# iso_GPIO_4in_4out.net
KiCad netlist of a schematic drawn in Altium Designer
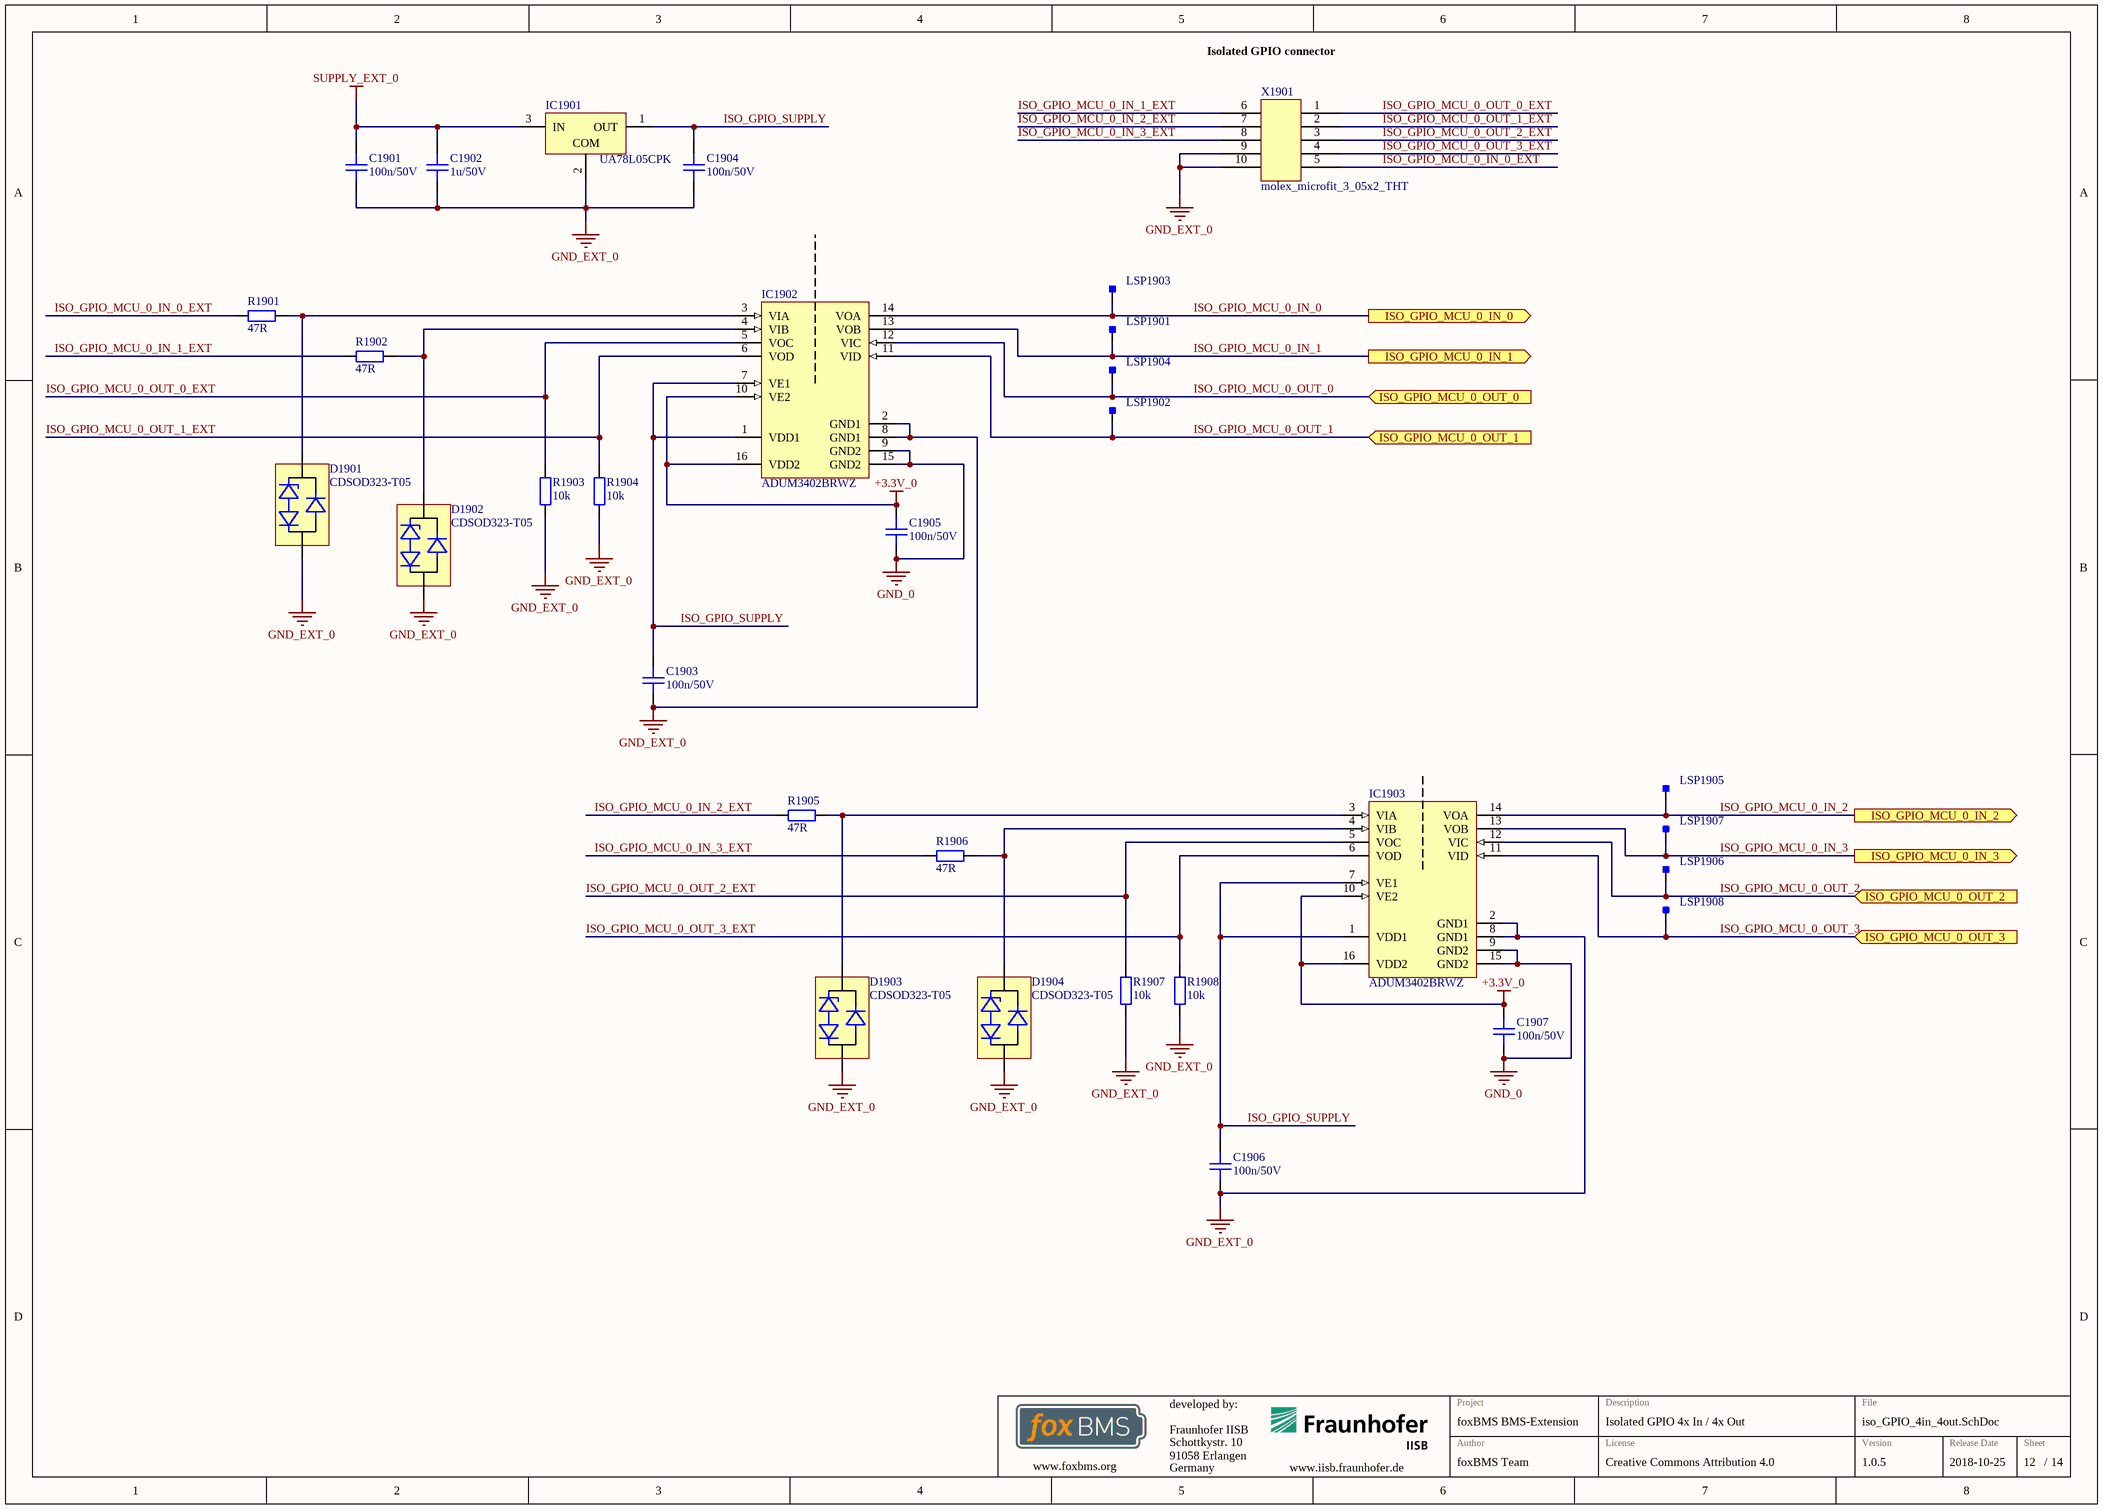
[diagram p0: iso_GPIO_4in_4out.SchDoc]

(export (version "E")
  (design (tool "Eeschema 10.0.6"))
  (components
    (comp (ref "C1901")
      (value "100n/50V")
      (footprint "CAPC1608X08N")
      (description "MLCC")
      (fields (field (name "PART NUMBER") "gen_C_ceramic_100n_50V_X7R_0603"))
      (libsource (lib "OE750") (part "C"))
    )
    (comp (ref "C1902")
      (value "1u/50V")
      (footprint "CAPC1608X08N")
      (description "MLCC")
      (fields (field (name "PART NUMBER") "gen_C_ceramic_1u_50V_X7R_0603") (field (name "TOLERANCE") "± 10%"))
      (libsource (lib "OE750") (part "C"))
    )
    (comp (ref "C1903")
      (value "100n/50V")
      (footprint "CAPC1608X08N")
      (description "MLCC")
      (fields (field (name "PART NUMBER") "gen_C_ceramic_100n_50V_X7R_0603"))
      (libsource (lib "OE750") (part "C"))
    )
    (comp (ref "C1904")
      (value "100n/50V")
      (footprint "CAPC1608X08N")
      (description "MLCC")
      (fields (field (name "PART NUMBER") "gen_C_ceramic_100n_50V_X7R_0603"))
      (libsource (lib "OE750") (part "C"))
    )
    (comp (ref "C1905")
      (value "100n/50V")
      (footprint "CAPC1608X08N")
      (description "MLCC")
      (fields (field (name "PART NUMBER") "gen_C_ceramic_100n_50V_X7R_0603"))
      (libsource (lib "OE750") (part "C"))
    )
    (comp (ref "C1906")
      (value "100n/50V")
      (footprint "CAPC1608X08N")
      (description "MLCC")
      (fields (field (name "PART NUMBER") "gen_C_ceramic_100n_50V_X7R_0603"))
      (libsource (lib "OE750") (part "C"))
    )
    (comp (ref "C1907")
      (value "100n/50V")
      (footprint "CAPC1608X08N")
      (description "MLCC")
      (fields (field (name "PART NUMBER") "gen_C_ceramic_100n_50V_X7R_0603"))
      (libsource (lib "OE750") (part "C"))
    )
    (comp (ref "D1901")
      (value "CDSOD323-T05")
      (footprint "SODFL250X110-2N")
      (description "TVS Diode, CDSOD323 Series, Unidirectional, 5 V, 18.3 V, SOD-323, 2 Pins")
      (fields (field (name "MANUFACTURER") "Bourns"))
      (libsource (lib "OE750") (part "D_TVS_uni"))
    )
    (comp (ref "D1902")
      (value "CDSOD323-T05")
      (footprint "SODFL250X110-2N")
      (description "TVS Diode, CDSOD323 Series, Unidirectional, 5 V, 18.3 V, SOD-323, 2 Pins")
      (fields (field (name "MANUFACTURER") "Bourns"))
      (libsource (lib "OE750") (part "D_TVS_uni"))
    )
    (comp (ref "D1903")
      (value "CDSOD323-T05")
      (footprint "SODFL250X110-2N")
      (description "TVS Diode, CDSOD323 Series, Unidirectional, 5 V, 18.3 V, SOD-323, 2 Pins")
      (fields (field (name "MANUFACTURER") "Bourns"))
      (libsource (lib "OE750") (part "D_TVS_uni"))
    )
    (comp (ref "D1904")
      (value "CDSOD323-T05")
      (footprint "SODFL250X110-2N")
      (description "TVS Diode, CDSOD323 Series, Unidirectional, 5 V, 18.3 V, SOD-323, 2 Pins")
      (fields (field (name "MANUFACTURER") "Bourns"))
      (libsource (lib "OE750") (part "D_TVS_uni"))
    )
    (comp (ref "IC1901")
      (value "UA78L05CPK")
      (footprint "PK0003A_L")
      (fields (field (name "MANUFACTURER") "TexasInstruments"))
      (libsource (lib "Altium Content Vault") (part "TI-UA78L05-PK-3"))
    )
    (comp (ref "IC1902")
      (value "ADUM3402BRWZ")
      (footprint "ADI-RW-16_N")
      (fields (field (name "MANUFACTURER") "Analog Devices"))
      (libsource (lib "Altium Content Vault") (part "ADI-ADUMXXX2-XX-16"))
    )
    (comp (ref "IC1903")
      (value "ADUM3402BRWZ")
      (footprint "ADI-RW-16_N")
      (fields (field (name "MANUFACTURER") "Analog Devices"))
      (libsource (lib "Altium Content Vault") (part "ADI-ADUMXXX2-XX-16"))
    )
    (comp (ref "LSP1901")
      (value "Testpoint_Square")
      (footprint "Testpoint_S1")
      (description "Testpoint, square")
      (libsource (lib "OE750") (part "Testpoint_Square"))
    )
    (comp (ref "LSP1902")
      (value "Testpoint_Square")
      (footprint "Testpoint_S1")
      (description "Testpoint, square")
      (libsource (lib "OE750") (part "Testpoint_Square"))
    )
    (comp (ref "LSP1903")
      (value "Testpoint_Square")
      (footprint "Testpoint_S1")
      (description "Testpoint, square")
      (libsource (lib "OE750") (part "Testpoint_Square"))
    )
    (comp (ref "LSP1904")
      (value "Testpoint_Square")
      (footprint "Testpoint_S1")
      (description "Testpoint, square")
      (libsource (lib "OE750") (part "Testpoint_Square"))
    )
    (comp (ref "LSP1905")
      (value "Testpoint_Square")
      (footprint "Testpoint_S1")
      (description "Testpoint, square")
      (libsource (lib "OE750") (part "Testpoint_Square"))
    )
    (comp (ref "LSP1906")
      (value "Testpoint_Square")
      (footprint "Testpoint_S1")
      (description "Testpoint, square")
      (libsource (lib "OE750") (part "Testpoint_Square"))
    )
    (comp (ref "LSP1907")
      (value "Testpoint_Square")
      (footprint "Testpoint_S1")
      (description "Testpoint, square")
      (libsource (lib "OE750") (part "Testpoint_Square"))
    )
    (comp (ref "LSP1908")
      (value "Testpoint_Square")
      (footprint "Testpoint_S1")
      (description "Testpoint, square")
      (libsource (lib "OE750") (part "Testpoint_Square"))
    )
    (comp (ref "R1901")
      (value "47R")
      (footprint "RESC1608X05N")
      (description "SMD Resistor 47R 0603")
      (fields (field (name "PART NUMBER") "gen_R_47R_0603") (field (name "TOLERANCE") "1%"))
      (libsource (lib "OE750") (part "R"))
    )
    (comp (ref "R1902")
      (value "47R")
      (footprint "RESC1608X05N")
      (description "SMD Resistor 47R 0603")
      (fields (field (name "PART NUMBER") "gen_R_47R_0603") (field (name "TOLERANCE") "1%"))
      (libsource (lib "OE750") (part "R"))
    )
    (comp (ref "R1903")
      (value "10k")
      (footprint "RESC1608X05N")
      (description "SMD Resistor 10k 0603")
      (fields (field (name "PART NUMBER") "gen_R_10k_0603") (field (name "TOLERANCE") "1%"))
      (libsource (lib "OE750") (part "R"))
    )
    (comp (ref "R1904")
      (value "10k")
      (footprint "RESC1608X05N")
      (description "SMD Resistor 10k 0603")
      (fields (field (name "PART NUMBER") "gen_R_10k_0603") (field (name "TOLERANCE") "1%"))
      (libsource (lib "OE750") (part "R"))
    )
    (comp (ref "R1905")
      (value "47R")
      (footprint "RESC1608X05N")
      (description "SMD Resistor 47R 0603")
      (fields (field (name "PART NUMBER") "gen_R_47R_0603") (field (name "TOLERANCE") "1%"))
      (libsource (lib "OE750") (part "R"))
    )
    (comp (ref "R1906")
      (value "47R")
      (footprint "RESC1608X05N")
      (description "SMD Resistor 47R 0603")
      (fields (field (name "PART NUMBER") "gen_R_47R_0603") (field (name "TOLERANCE") "1%"))
      (libsource (lib "OE750") (part "R"))
    )
    (comp (ref "R1907")
      (value "10k")
      (footprint "RESC1608X05N")
      (description "SMD Resistor 10k 0603")
      (fields (field (name "PART NUMBER") "gen_R_10k_0603") (field (name "TOLERANCE") "1%"))
      (libsource (lib "OE750") (part "R"))
    )
    (comp (ref "R1908")
      (value "10k")
      (footprint "RESC1608X05N")
      (description "SMD Resistor 10k 0603")
      (fields (field (name "PART NUMBER") "gen_R_10k_0603") (field (name "TOLERANCE") "1%"))
      (libsource (lib "OE750") (part "R"))
    )
    (comp (ref "X1901")
      (value "molex_microfit_3_05x2_THT")
      (footprint "43045-1021")
      (fields (field (name "MANUFACTURER") "Molex"))
      (libsource (lib "OE750") (part "X5x2"))
    )
  )
  (nets
    (net (code "1") (name "+3.3V_0") (class "Default")
      (node (ref "C1905") (pin "1") (pinfunction "1_1") (pintype "passive"))
      (node (ref "C1907") (pin "1") (pinfunction "1_1") (pintype "passive"))
      (node (ref "IC1902") (pin "10") (pinfunction "VE2_10") (pintype "input"))
      (node (ref "IC1902") (pin "16") (pinfunction "VDD2_16") (pintype "power_in"))
      (node (ref "IC1903") (pin "10") (pinfunction "VE2_10") (pintype "input"))
      (node (ref "IC1903") (pin "16") (pinfunction "VDD2_16") (pintype "power_in"))
    )
    (net (code "2") (name "/ISO_GPIO_MCU_0_IN_0") (class "Default")
      (node (ref "IC1902") (pin "14") (pinfunction "VOA_14") (pintype "tri_state"))
      (node (ref "LSP1903") (pin "1") (pinfunction "1_1") (pintype "passive"))
    )
    (net (code "3") (name "/ISO_GPIO_MCU_0_IN_0_EXT") (class "Default")
      (node (ref "R1901") (pin "2") (pinfunction "2_2") (pintype "passive"))
      (node (ref "X1901") (pin "5") (pintype "passive"))
    )
    (net (code "4") (name "/ISO_GPIO_MCU_0_IN_1") (class "Default")
      (node (ref "IC1902") (pin "13") (pinfunction "VOB_13") (pintype "tri_state"))
      (node (ref "LSP1901") (pin "1") (pinfunction "1_1") (pintype "passive"))
    )
    (net (code "5") (name "/ISO_GPIO_MCU_0_IN_1_EXT") (class "Default")
      (node (ref "R1902") (pin "2") (pinfunction "2_2") (pintype "passive"))
      (node (ref "X1901") (pin "6") (pintype "passive"))
    )
    (net (code "6") (name "/ISO_GPIO_MCU_0_IN_2") (class "Default")
      (node (ref "IC1903") (pin "14") (pinfunction "VOA_14") (pintype "tri_state"))
      (node (ref "LSP1905") (pin "1") (pinfunction "1_1") (pintype "passive"))
    )
    (net (code "7") (name "/ISO_GPIO_MCU_0_IN_2_EXT") (class "Default")
      (node (ref "R1905") (pin "2") (pinfunction "2_2") (pintype "passive"))
      (node (ref "X1901") (pin "7") (pintype "passive"))
    )
    (net (code "8") (name "/ISO_GPIO_MCU_0_IN_3") (class "Default")
      (node (ref "IC1903") (pin "13") (pinfunction "VOB_13") (pintype "tri_state"))
      (node (ref "LSP1907") (pin "1") (pinfunction "1_1") (pintype "passive"))
    )
    (net (code "9") (name "/ISO_GPIO_MCU_0_IN_3_EXT") (class "Default")
      (node (ref "R1906") (pin "2") (pinfunction "2_2") (pintype "passive"))
      (node (ref "X1901") (pin "8") (pintype "passive"))
    )
    (net (code "10") (name "/ISO_GPIO_MCU_0_OUT_0") (class "Default")
      (node (ref "IC1902") (pin "12") (pinfunction "VIC_12") (pintype "input"))
      (node (ref "LSP1904") (pin "1") (pinfunction "1_1") (pintype "passive"))
    )
    (net (code "11") (name "/ISO_GPIO_MCU_0_OUT_0_EXT") (class "Default")
      (node (ref "IC1902") (pin "5") (pinfunction "VOC_5") (pintype "tri_state"))
      (node (ref "R1903") (pin "2") (pinfunction "2_2") (pintype "passive"))
      (node (ref "X1901") (pin "1") (pintype "passive"))
    )
    (net (code "12") (name "/ISO_GPIO_MCU_0_OUT_1") (class "Default")
      (node (ref "IC1902") (pin "11") (pinfunction "VID_11") (pintype "input"))
      (node (ref "LSP1902") (pin "1") (pinfunction "1_1") (pintype "passive"))
    )
    (net (code "13") (name "/ISO_GPIO_MCU_0_OUT_1_EXT") (class "Default")
      (node (ref "IC1902") (pin "6") (pinfunction "VOD_6") (pintype "tri_state"))
      (node (ref "R1904") (pin "2") (pinfunction "2_2") (pintype "passive"))
      (node (ref "X1901") (pin "2") (pintype "passive"))
    )
    (net (code "14") (name "/ISO_GPIO_MCU_0_OUT_2") (class "Default")
      (node (ref "IC1903") (pin "12") (pinfunction "VIC_12") (pintype "input"))
      (node (ref "LSP1906") (pin "1") (pinfunction "1_1") (pintype "passive"))
    )
    (net (code "15") (name "/ISO_GPIO_MCU_0_OUT_2_EXT") (class "Default")
      (node (ref "IC1903") (pin "5") (pinfunction "VOC_5") (pintype "tri_state"))
      (node (ref "R1907") (pin "2") (pinfunction "2_2") (pintype "passive"))
      (node (ref "X1901") (pin "3") (pintype "passive"))
    )
    (net (code "16") (name "/ISO_GPIO_MCU_0_OUT_3") (class "Default")
      (node (ref "IC1903") (pin "11") (pinfunction "VID_11") (pintype "input"))
      (node (ref "LSP1908") (pin "1") (pinfunction "1_1") (pintype "passive"))
    )
    (net (code "17") (name "/ISO_GPIO_MCU_0_OUT_3_EXT") (class "Default")
      (node (ref "IC1903") (pin "6") (pinfunction "VOD_6") (pintype "tri_state"))
      (node (ref "R1908") (pin "2") (pinfunction "2_2") (pintype "passive"))
      (node (ref "X1901") (pin "4") (pintype "passive"))
    )
    (net (code "18") (name "/ISO_GPIO_SUPPLY") (class "Default")
      (node (ref "C1903") (pin "1") (pinfunction "1_1") (pintype "passive"))
      (node (ref "C1904") (pin "1") (pinfunction "1_1") (pintype "passive"))
      (node (ref "C1906") (pin "1") (pinfunction "1_1") (pintype "passive"))
      (node (ref "IC1901") (pin "1") (pinfunction "OUT_1") (pintype "power_in"))
      (node (ref "IC1902") (pin "1") (pinfunction "VDD1_1") (pintype "power_in"))
      (node (ref "IC1902") (pin "7") (pinfunction "VE1_7") (pintype "input"))
      (node (ref "IC1903") (pin "1") (pinfunction "VDD1_1") (pintype "power_in"))
      (node (ref "IC1903") (pin "7") (pinfunction "VE1_7") (pintype "input"))
    )
    (net (code "19") (name "GND_0") (class "Default")
      (node (ref "C1905") (pin "2") (pinfunction "2_2") (pintype "passive"))
      (node (ref "C1907") (pin "2") (pinfunction "2_2") (pintype "passive"))
      (node (ref "IC1902") (pin "15") (pinfunction "GND2_15") (pintype "power_in"))
      (node (ref "IC1902") (pin "9") (pinfunction "GND2_9") (pintype "power_in"))
      (node (ref "IC1903") (pin "15") (pinfunction "GND2_15") (pintype "power_in"))
      (node (ref "IC1903") (pin "9") (pinfunction "GND2_9") (pintype "power_in"))
    )
    (net (code "20") (name "GND_EXT_0") (class "Default")
      (node (ref "C1901") (pin "2") (pinfunction "2_2") (pintype "passive"))
      (node (ref "C1902") (pin "2") (pinfunction "2_2") (pintype "passive"))
      (node (ref "C1903") (pin "2") (pinfunction "2_2") (pintype "passive"))
      (node (ref "C1904") (pin "2") (pinfunction "2_2") (pintype "passive"))
      (node (ref "C1906") (pin "2") (pinfunction "2_2") (pintype "passive"))
      (node (ref "D1901") (pin "2") (pinfunction "A_2") (pintype "passive"))
      (node (ref "D1902") (pin "2") (pinfunction "A_2") (pintype "passive"))
      (node (ref "D1903") (pin "2") (pinfunction "A_2") (pintype "passive"))
      (node (ref "D1904") (pin "2") (pinfunction "A_2") (pintype "passive"))
      (node (ref "IC1901") (pin "2") (pinfunction "COM_2") (pintype "power_in"))
      (node (ref "IC1902") (pin "2") (pinfunction "GND1_2") (pintype "power_in"))
      (node (ref "IC1902") (pin "8") (pinfunction "GND1_8") (pintype "power_in"))
      (node (ref "IC1903") (pin "2") (pinfunction "GND1_2") (pintype "power_in"))
      (node (ref "IC1903") (pin "8") (pinfunction "GND1_8") (pintype "power_in"))
      (node (ref "R1903") (pin "1") (pinfunction "1_1") (pintype "passive"))
      (node (ref "R1904") (pin "1") (pinfunction "1_1") (pintype "passive"))
      (node (ref "R1907") (pin "1") (pinfunction "1_1") (pintype "passive"))
      (node (ref "R1908") (pin "1") (pinfunction "1_1") (pintype "passive"))
      (node (ref "X1901") (pin "10") (pintype "passive"))
      (node (ref "X1901") (pin "9") (pintype "passive"))
    )
    (net (code "21") (name "Net-(D1901-K)") (class "Default")
      (node (ref "D1901") (pin "1") (pinfunction "K_1") (pintype "passive"))
      (node (ref "IC1902") (pin "3") (pinfunction "VIA_3") (pintype "input"))
      (node (ref "R1901") (pin "1") (pinfunction "1_1") (pintype "passive"))
    )
    (net (code "22") (name "Net-(D1902-K)") (class "Default")
      (node (ref "D1902") (pin "1") (pinfunction "K_1") (pintype "passive"))
      (node (ref "IC1902") (pin "4") (pinfunction "VIB_4") (pintype "input"))
      (node (ref "R1902") (pin "1") (pinfunction "1_1") (pintype "passive"))
    )
    (net (code "23") (name "Net-(D1903-K)") (class "Default")
      (node (ref "D1903") (pin "1") (pinfunction "K_1") (pintype "passive"))
      (node (ref "IC1903") (pin "3") (pinfunction "VIA_3") (pintype "input"))
      (node (ref "R1905") (pin "1") (pinfunction "1_1") (pintype "passive"))
    )
    (net (code "24") (name "Net-(D1904-K)") (class "Default")
      (node (ref "D1904") (pin "1") (pinfunction "K_1") (pintype "passive"))
      (node (ref "IC1903") (pin "4") (pinfunction "VIB_4") (pintype "input"))
      (node (ref "R1906") (pin "1") (pinfunction "1_1") (pintype "passive"))
    )
    (net (code "25") (name "SUPPLY_EXT_0") (class "Default")
      (node (ref "C1901") (pin "1") (pinfunction "1_1") (pintype "passive"))
      (node (ref "C1902") (pin "1") (pinfunction "1_1") (pintype "passive"))
      (node (ref "IC1901") (pin "3") (pinfunction "IN_3") (pintype "power_in"))
    )
  )
)
